# level_shift.net
KiCad netlist of a schematic drawn in EAGLE
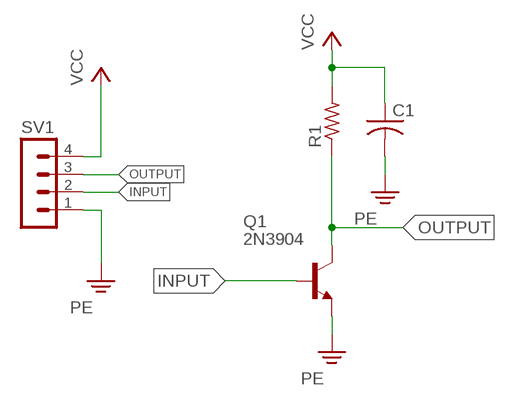
[diagram p0: schematic, sheet 1]

(export (version "E")
  (design (tool "Eeschema 10.0.6"))
  (components
    (comp (ref "C1")
      (value "C-US025-030X050")
      (footprint "eagle-import:C025-030X050")
      (libsource (lib "eagle-import") (part "C-US025-030X050"))
    )
    (comp (ref "Q1")
      (value "2N3904")
      (footprint "eagle-import:TO-92")
      (libsource (lib "eagle-import") (part "2N3904"))
    )
    (comp (ref "R1")
      (value "R-US_0204/7")
      (footprint "eagle-import:0204_7")
      (libsource (lib "eagle-import") (part "R-US_0204/7"))
    )
    (comp (ref "SV1")
      (value "MA04-1")
      (footprint "eagle-import:MA04-1")
      (libsource (lib "eagle-import") (part "MA04-1"))
    )
  )
  (nets
    (net (code "1") (name "INPUT") (class "Default")
      (node (ref "Q1") (pin "B") (pinfunction "B_B") (pintype "passive"))
      (node (ref "SV1") (pin "2") (pinfunction "2_2") (pintype "passive"))
    )
    (net (code "2") (name "OUTPUT") (class "Default")
      (node (ref "Q1") (pin "C") (pinfunction "C_C") (pintype "passive"))
      (node (ref "R1") (pin "1") (pinfunction "1_1") (pintype "passive"))
      (node (ref "SV1") (pin "3") (pinfunction "3_3") (pintype "passive"))
    )
    (net (code "3") (name "PE") (class "Default")
      (node (ref "C1") (pin "2") (pinfunction "2_2") (pintype "passive"))
      (node (ref "Q1") (pin "E") (pinfunction "E_E") (pintype "passive"))
      (node (ref "SV1") (pin "1") (pinfunction "1_1") (pintype "passive"))
    )
    (net (code "4") (name "VCC") (class "Default")
      (node (ref "C1") (pin "1") (pinfunction "1_1") (pintype "passive"))
      (node (ref "R1") (pin "2") (pinfunction "2_2") (pintype "passive"))
      (node (ref "SV1") (pin "4") (pinfunction "4_4") (pintype "passive"))
    )
  )
)
